# PIN2DMD.net
KiCad netlist of a schematic drawn in EAGLE
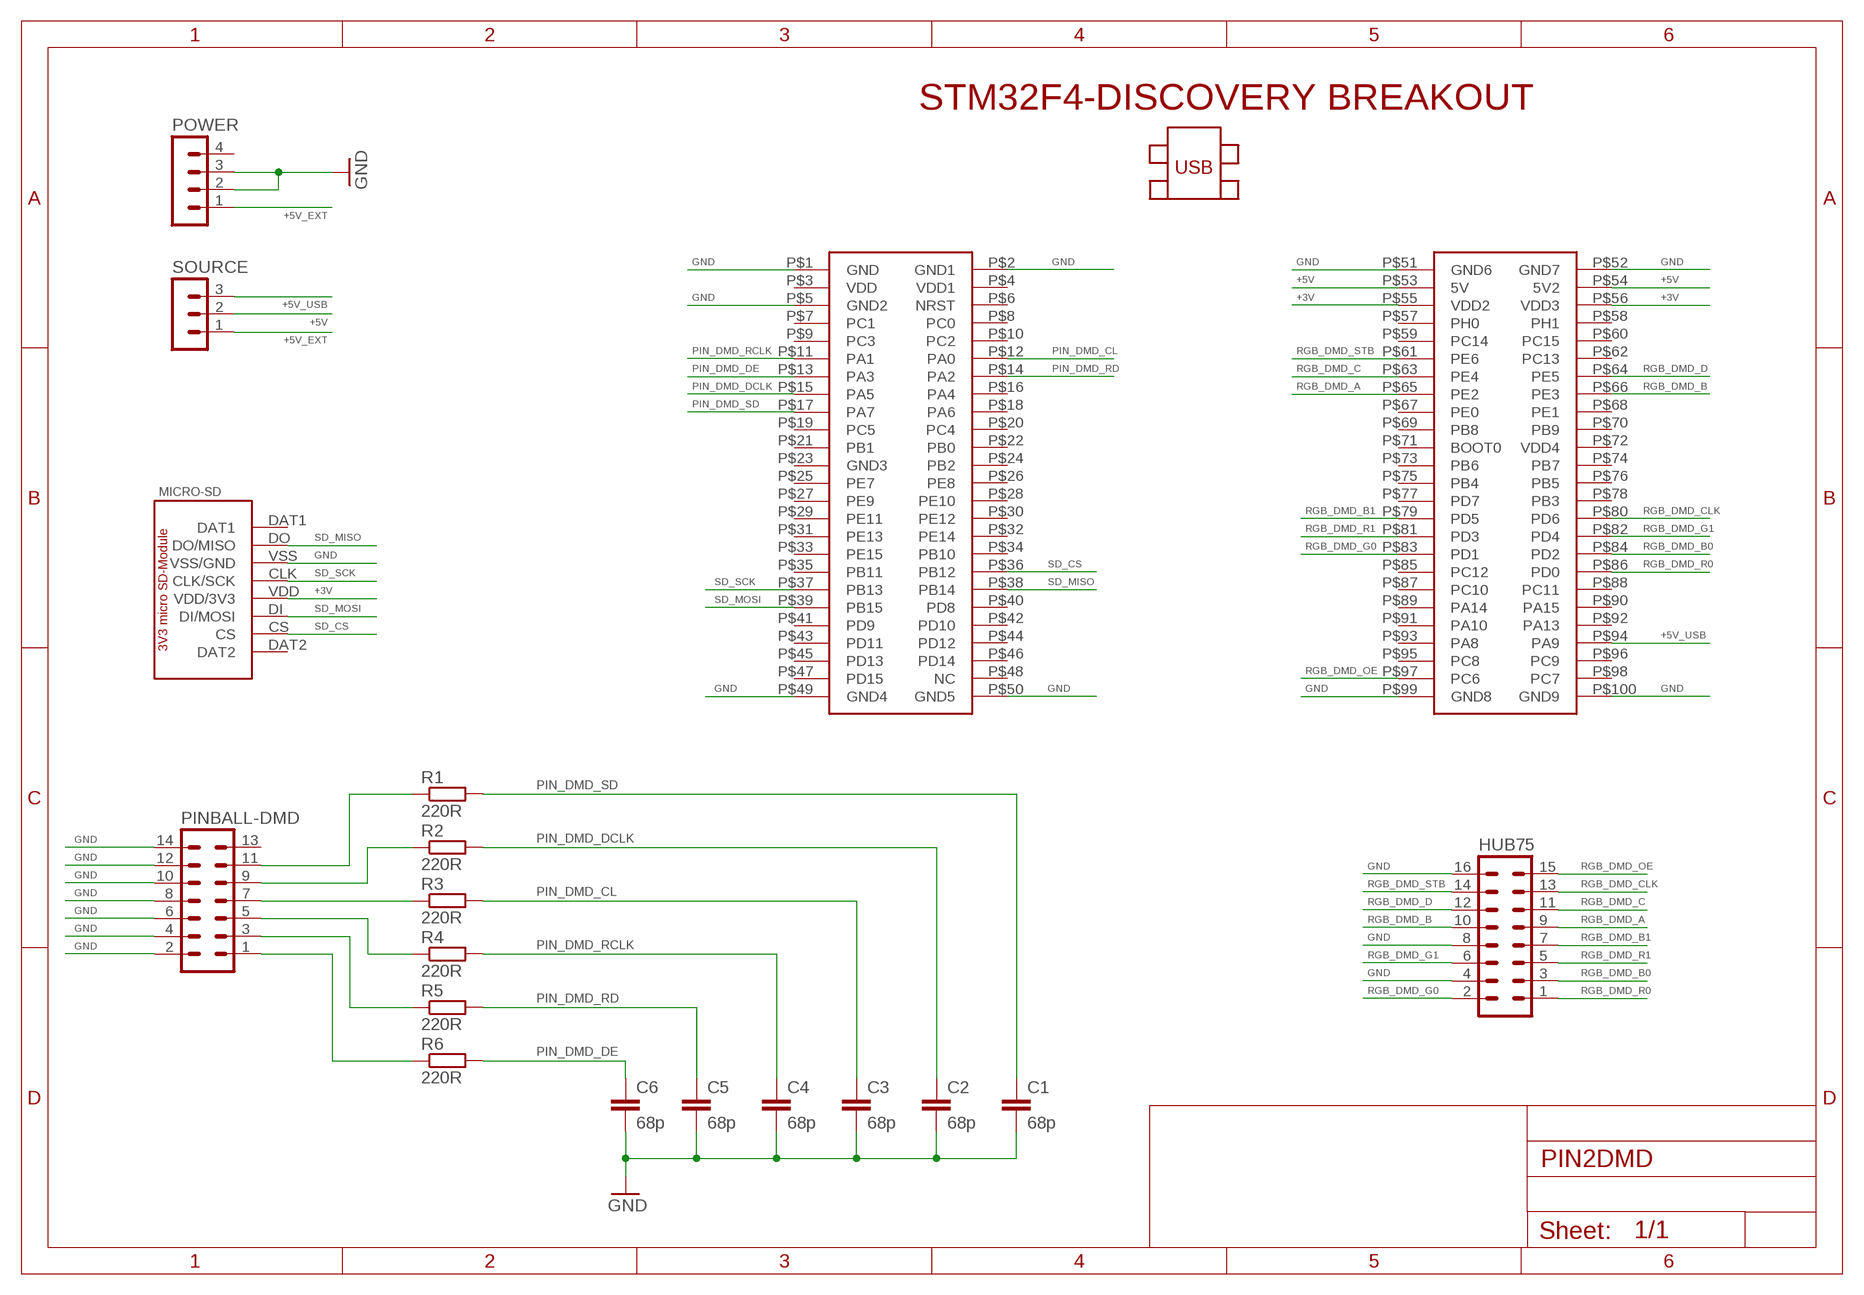
[diagram p0: schematic, sheet 1]

(export (version "E")
  (design (tool "Eeschema 10.0.6"))
  (components
    (comp (ref "C1")
      (value "68p")
      (footprint "eagle-import:C025-024X044")
      (libsource (lib "eagle-import") (part "C-EU025-024X044"))
    )
    (comp (ref "C2")
      (value "68p")
      (footprint "eagle-import:C025-024X044")
      (libsource (lib "eagle-import") (part "C-EU025-024X044"))
    )
    (comp (ref "C3")
      (value "68p")
      (footprint "eagle-import:C025-024X044")
      (libsource (lib "eagle-import") (part "C-EU025-024X044"))
    )
    (comp (ref "C4")
      (value "68p")
      (footprint "eagle-import:C025-024X044")
      (libsource (lib "eagle-import") (part "C-EU025-024X044"))
    )
    (comp (ref "C5")
      (value "68p")
      (footprint "eagle-import:C025-024X044")
      (libsource (lib "eagle-import") (part "C-EU025-024X044"))
    )
    (comp (ref "C6")
      (value "68p")
      (footprint "eagle-import:C025-024X044")
      (libsource (lib "eagle-import") (part "C-EU025-024X044"))
    )
    (comp (ref "HUB75")
      (value "MA08-2")
      (footprint "eagle-import:MA08-2")
      (libsource (lib "eagle-import") (part "MA08-2"))
    )
    (comp (ref "MICRO-SD")
      (value "SPI_SDCARD_3V3_MICRO")
      (footprint "eagle-import:SPI_SDCARD_3V3_MICRO")
      (libsource (lib "eagle-import") (part "SPI_SDCARD_3V3_MICRO"))
    )
    (comp (ref "PINBALL-DMD")
      (value "MA07-2")
      (footprint "eagle-import:MA07-2")
      (libsource (lib "eagle-import") (part "MA07-2"))
    )
    (comp (ref "POWER")
      (value "MA04-1")
      (footprint "eagle-import:MA04-1")
      (libsource (lib "eagle-import") (part "MA04-1"))
    )
    (comp (ref "R1")
      (value "220R")
      (footprint "eagle-import:0207_10")
      (libsource (lib "eagle-import") (part "R-EU_0207/10"))
    )
    (comp (ref "R2")
      (value "220R")
      (footprint "eagle-import:0207_10")
      (libsource (lib "eagle-import") (part "R-EU_0207/10"))
    )
    (comp (ref "R3")
      (value "220R")
      (footprint "eagle-import:0207_10")
      (libsource (lib "eagle-import") (part "R-EU_0207/10"))
    )
    (comp (ref "R4")
      (value "220R")
      (footprint "eagle-import:0207_10")
      (libsource (lib "eagle-import") (part "R-EU_0207/10"))
    )
    (comp (ref "R5")
      (value "220R")
      (footprint "eagle-import:0207_10")
      (libsource (lib "eagle-import") (part "R-EU_0207/10"))
    )
    (comp (ref "R6")
      (value "220R")
      (footprint "eagle-import:0207_10")
      (libsource (lib "eagle-import") (part "R-EU_0207/10"))
    )
    (comp (ref "SOURCE")
      (value "MA03-1")
      (footprint "eagle-import:MA03-1")
      (libsource (lib "eagle-import") (part "MA03-1"))
    )
    (comp (ref "U$1")
      (value "STM32F4-DISCOVERY")
      (footprint "eagle-import:STM32F4-DISCOVERY")
      (libsource (lib "eagle-import") (part "STM32F4-DISCOVERY"))
    )
  )
  (nets
    (net (code "1") (name "/+3V") (class "Default")
      (node (ref "MICRO-SD") (pin "VDD") (pinfunction "VDD/3V3_VDD") (pintype "input"))
      (node (ref "U$1") (pin "P$55") (pinfunction "VDD2_P$55") (pintype "bidirectional"))
      (node (ref "U$1") (pin "P$56") (pinfunction "VDD3_P$56") (pintype "bidirectional"))
    )
    (net (code "2") (name "/+5V") (class "Default")
      (node (ref "SOURCE") (pin "2") (pinfunction "2_2") (pintype "passive"))
      (node (ref "U$1") (pin "P$53") (pinfunction "5V_P$53") (pintype "bidirectional"))
      (node (ref "U$1") (pin "P$54") (pinfunction "5V2_P$54") (pintype "bidirectional"))
    )
    (net (code "3") (name "/+5V_EXT") (class "Default")
      (node (ref "POWER") (pin "1") (pinfunction "1_1") (pintype "passive"))
      (node (ref "SOURCE") (pin "1") (pinfunction "1_1") (pintype "passive"))
    )
    (net (code "4") (name "/+5V_USB") (class "Default")
      (node (ref "SOURCE") (pin "3") (pinfunction "3_3") (pintype "passive"))
      (node (ref "U$1") (pin "P$94") (pinfunction "PA9_P$94") (pintype "bidirectional"))
    )
    (net (code "5") (name "/PIN_DMD_CL") (class "Default")
      (node (ref "C3") (pin "1") (pinfunction "1_1") (pintype "passive"))
      (node (ref "R3") (pin "2") (pinfunction "2_2") (pintype "passive"))
      (node (ref "U$1") (pin "P$12") (pinfunction "PA0_P$12") (pintype "bidirectional"))
    )
    (net (code "6") (name "/PIN_DMD_DCLK") (class "Default")
      (node (ref "C2") (pin "1") (pinfunction "1_1") (pintype "passive"))
      (node (ref "R2") (pin "2") (pinfunction "2_2") (pintype "passive"))
      (node (ref "U$1") (pin "P$15") (pinfunction "PA5_P$15") (pintype "bidirectional"))
    )
    (net (code "7") (name "/PIN_DMD_DE") (class "Default")
      (node (ref "C6") (pin "1") (pinfunction "1_1") (pintype "passive"))
      (node (ref "R6") (pin "2") (pinfunction "2_2") (pintype "passive"))
      (node (ref "U$1") (pin "P$13") (pinfunction "PA3_P$13") (pintype "bidirectional"))
    )
    (net (code "8") (name "/PIN_DMD_RCLK") (class "Default")
      (node (ref "C4") (pin "1") (pinfunction "1_1") (pintype "passive"))
      (node (ref "R4") (pin "2") (pinfunction "2_2") (pintype "passive"))
      (node (ref "U$1") (pin "P$11") (pinfunction "PA1_P$11") (pintype "bidirectional"))
    )
    (net (code "9") (name "/PIN_DMD_RD") (class "Default")
      (node (ref "C5") (pin "1") (pinfunction "1_1") (pintype "passive"))
      (node (ref "R5") (pin "2") (pinfunction "2_2") (pintype "passive"))
      (node (ref "U$1") (pin "P$14") (pinfunction "PA2_P$14") (pintype "bidirectional"))
    )
    (net (code "10") (name "/PIN_DMD_SD") (class "Default")
      (node (ref "C1") (pin "1") (pinfunction "1_1") (pintype "passive"))
      (node (ref "R1") (pin "2") (pinfunction "2_2") (pintype "passive"))
      (node (ref "U$1") (pin "P$17") (pinfunction "PA7_P$17") (pintype "bidirectional"))
    )
    (net (code "11") (name "/RGB_DMD_A") (class "Default")
      (node (ref "HUB75") (pin "9") (pinfunction "9_9") (pintype "passive"))
      (node (ref "U$1") (pin "P$65") (pinfunction "PE2_P$65") (pintype "bidirectional"))
    )
    (net (code "12") (name "/RGB_DMD_B") (class "Default")
      (node (ref "HUB75") (pin "10") (pinfunction "10_10") (pintype "passive"))
      (node (ref "U$1") (pin "P$66") (pinfunction "PE3_P$66") (pintype "bidirectional"))
    )
    (net (code "13") (name "/RGB_DMD_B0") (class "Default")
      (node (ref "HUB75") (pin "3") (pinfunction "3_3") (pintype "passive"))
      (node (ref "U$1") (pin "P$84") (pinfunction "PD2_P$84") (pintype "bidirectional"))
    )
    (net (code "14") (name "/RGB_DMD_B1") (class "Default")
      (node (ref "HUB75") (pin "7") (pinfunction "7_7") (pintype "passive"))
      (node (ref "U$1") (pin "P$79") (pinfunction "PD5_P$79") (pintype "bidirectional"))
    )
    (net (code "15") (name "/RGB_DMD_C") (class "Default")
      (node (ref "HUB75") (pin "11") (pinfunction "11_11") (pintype "passive"))
      (node (ref "U$1") (pin "P$63") (pinfunction "PE4_P$63") (pintype "bidirectional"))
    )
    (net (code "16") (name "/RGB_DMD_CLK") (class "Default")
      (node (ref "HUB75") (pin "13") (pinfunction "13_13") (pintype "passive"))
      (node (ref "U$1") (pin "P$80") (pinfunction "PD6_P$80") (pintype "bidirectional"))
    )
    (net (code "17") (name "/RGB_DMD_D") (class "Default")
      (node (ref "HUB75") (pin "12") (pinfunction "12_12") (pintype "passive"))
      (node (ref "U$1") (pin "P$64") (pinfunction "PE5_P$64") (pintype "bidirectional"))
    )
    (net (code "18") (name "/RGB_DMD_G0") (class "Default")
      (node (ref "HUB75") (pin "2") (pinfunction "2_2") (pintype "passive"))
      (node (ref "U$1") (pin "P$83") (pinfunction "PD1_P$83") (pintype "bidirectional"))
    )
    (net (code "19") (name "/RGB_DMD_G1") (class "Default")
      (node (ref "HUB75") (pin "6") (pinfunction "6_6") (pintype "passive"))
      (node (ref "U$1") (pin "P$82") (pinfunction "PD4_P$82") (pintype "bidirectional"))
    )
    (net (code "20") (name "/RGB_DMD_OE") (class "Default")
      (node (ref "HUB75") (pin "15") (pinfunction "15_15") (pintype "passive"))
      (node (ref "U$1") (pin "P$97") (pinfunction "PC6_P$97") (pintype "bidirectional"))
    )
    (net (code "21") (name "/RGB_DMD_R0") (class "Default")
      (node (ref "HUB75") (pin "1") (pinfunction "1_1") (pintype "passive"))
      (node (ref "U$1") (pin "P$86") (pinfunction "PD0_P$86") (pintype "bidirectional"))
    )
    (net (code "22") (name "/RGB_DMD_R1") (class "Default")
      (node (ref "HUB75") (pin "5") (pinfunction "5_5") (pintype "passive"))
      (node (ref "U$1") (pin "P$81") (pinfunction "PD3_P$81") (pintype "bidirectional"))
    )
    (net (code "23") (name "/RGB_DMD_STB") (class "Default")
      (node (ref "HUB75") (pin "14") (pinfunction "14_14") (pintype "passive"))
      (node (ref "U$1") (pin "P$61") (pinfunction "PE6_P$61") (pintype "bidirectional"))
    )
    (net (code "24") (name "/SD_CS") (class "Default")
      (node (ref "MICRO-SD") (pin "CS") (pinfunction "CS_CS") (pintype "input"))
      (node (ref "U$1") (pin "P$36") (pinfunction "PB12_P$36") (pintype "bidirectional"))
    )
    (net (code "25") (name "/SD_MISO") (class "Default")
      (node (ref "MICRO-SD") (pin "DO") (pinfunction "DO/MISO_DO") (pintype "bidirectional"))
      (node (ref "U$1") (pin "P$38") (pinfunction "PB14_P$38") (pintype "bidirectional"))
    )
    (net (code "26") (name "/SD_MOSI") (class "Default")
      (node (ref "MICRO-SD") (pin "DI") (pinfunction "DI/MOSI_DI") (pintype "input"))
      (node (ref "U$1") (pin "P$39") (pinfunction "PB15_P$39") (pintype "bidirectional"))
    )
    (net (code "27") (name "/SD_SCK") (class "Default")
      (node (ref "MICRO-SD") (pin "CLK") (pinfunction "CLK/SCK_CLK") (pintype "input"))
      (node (ref "U$1") (pin "P$37") (pinfunction "PB13_P$37") (pintype "bidirectional"))
    )
    (net (code "28") (name "GND") (class "Default")
      (node (ref "C1") (pin "2") (pinfunction "2_2") (pintype "passive"))
      (node (ref "C2") (pin "2") (pinfunction "2_2") (pintype "passive"))
      (node (ref "C3") (pin "2") (pinfunction "2_2") (pintype "passive"))
      (node (ref "C4") (pin "2") (pinfunction "2_2") (pintype "passive"))
      (node (ref "C5") (pin "2") (pinfunction "2_2") (pintype "passive"))
      (node (ref "C6") (pin "2") (pinfunction "2_2") (pintype "passive"))
      (node (ref "HUB75") (pin "16") (pinfunction "16_16") (pintype "passive"))
      (node (ref "HUB75") (pin "4") (pinfunction "4_4") (pintype "passive"))
      (node (ref "HUB75") (pin "8") (pinfunction "8_8") (pintype "passive"))
      (node (ref "MICRO-SD") (pin "VSS") (pinfunction "VSS/GND_VSS") (pintype "input"))
      (node (ref "PINBALL-DMD") (pin "10") (pinfunction "10_10") (pintype "passive"))
      (node (ref "PINBALL-DMD") (pin "12") (pinfunction "12_12") (pintype "passive"))
      (node (ref "PINBALL-DMD") (pin "14") (pinfunction "14_14") (pintype "passive"))
      (node (ref "PINBALL-DMD") (pin "2") (pinfunction "2_2") (pintype "passive"))
      (node (ref "PINBALL-DMD") (pin "4") (pinfunction "4_4") (pintype "passive"))
      (node (ref "PINBALL-DMD") (pin "6") (pinfunction "6_6") (pintype "passive"))
      (node (ref "PINBALL-DMD") (pin "8") (pinfunction "8_8") (pintype "passive"))
      (node (ref "POWER") (pin "2") (pinfunction "2_2") (pintype "passive"))
      (node (ref "POWER") (pin "3") (pinfunction "3_3") (pintype "passive"))
      (node (ref "U$1") (pin "P$1") (pinfunction "GND_P$1") (pintype "bidirectional"))
      (node (ref "U$1") (pin "P$100") (pinfunction "GND9_P$100") (pintype "bidirectional"))
      (node (ref "U$1") (pin "P$2") (pinfunction "GND1_P$2") (pintype "bidirectional"))
      (node (ref "U$1") (pin "P$49") (pinfunction "GND4_P$49") (pintype "bidirectional"))
      (node (ref "U$1") (pin "P$5") (pinfunction "GND2_P$5") (pintype "bidirectional"))
      (node (ref "U$1") (pin "P$50") (pinfunction "GND5_P$50") (pintype "bidirectional"))
      (node (ref "U$1") (pin "P$51") (pinfunction "GND6_P$51") (pintype "bidirectional"))
      (node (ref "U$1") (pin "P$52") (pinfunction "GND7_P$52") (pintype "bidirectional"))
      (node (ref "U$1") (pin "P$99") (pinfunction "GND8_P$99") (pintype "bidirectional"))
    )
    (net (code "29") (name "Net-(PINBALL-DMD-Pad1)") (class "Default")
      (node (ref "PINBALL-DMD") (pin "1") (pinfunction "1_1") (pintype "passive"))
      (node (ref "R6") (pin "1") (pinfunction "1_1") (pintype "passive"))
    )
    (net (code "30") (name "Net-(PINBALL-DMD-Pad3)") (class "Default")
      (node (ref "PINBALL-DMD") (pin "3") (pinfunction "3_3") (pintype "passive"))
      (node (ref "R5") (pin "1") (pinfunction "1_1") (pintype "passive"))
    )
    (net (code "31") (name "Net-(PINBALL-DMD-Pad5)") (class "Default")
      (node (ref "PINBALL-DMD") (pin "5") (pinfunction "5_5") (pintype "passive"))
      (node (ref "R4") (pin "1") (pinfunction "1_1") (pintype "passive"))
    )
    (net (code "32") (name "Net-(PINBALL-DMD-Pad7)") (class "Default")
      (node (ref "PINBALL-DMD") (pin "7") (pinfunction "7_7") (pintype "passive"))
      (node (ref "R3") (pin "1") (pinfunction "1_1") (pintype "passive"))
    )
    (net (code "33") (name "Net-(PINBALL-DMD-Pad9)") (class "Default")
      (node (ref "PINBALL-DMD") (pin "9") (pinfunction "9_9") (pintype "passive"))
      (node (ref "R2") (pin "1") (pinfunction "1_1") (pintype "passive"))
    )
    (net (code "34") (name "Net-(PINBALL-DMD-Pad11)") (class "Default")
      (node (ref "PINBALL-DMD") (pin "11") (pinfunction "11_11") (pintype "passive"))
      (node (ref "R1") (pin "1") (pinfunction "1_1") (pintype "passive"))
    )
    (net (code "35") (name "unconnected-(MICRO-SD-PadDAT1)") (class "Default")
      (node (ref "MICRO-SD") (pin "DAT1") (pinfunction "DAT1_DAT1") (pintype "bidirectional"))
    )
    (net (code "36") (name "unconnected-(MICRO-SD-PadDAT2)") (class "Default")
      (node (ref "MICRO-SD") (pin "DAT2") (pinfunction "DAT2_DAT2") (pintype "input"))
    )
    (net (code "37") (name "unconnected-(PINBALL-DMD-Pad13)") (class "Default")
      (node (ref "PINBALL-DMD") (pin "13") (pinfunction "13_13") (pintype "passive"))
    )
    (net (code "38") (name "unconnected-(POWER-Pad4)") (class "Default")
      (node (ref "POWER") (pin "4") (pinfunction "4_4") (pintype "passive"))
    )
    (net (code "39") (name "unconnected-(U$1-BOOT0-PadP$71)") (class "Default")
      (node (ref "U$1") (pin "P$71") (pinfunction "BOOT0_P$71") (pintype "bidirectional"))
    )
    (net (code "40") (name "unconnected-(U$1-GND3-PadP$23)") (class "Default")
      (node (ref "U$1") (pin "P$23") (pinfunction "GND3_P$23") (pintype "bidirectional"))
    )
    (net (code "41") (name "unconnected-(U$1-NC-PadP$48)") (class "Default")
      (node (ref "U$1") (pin "P$48") (pinfunction "NC_P$48") (pintype "bidirectional"))
    )
    (net (code "42") (name "unconnected-(U$1-NRST-PadP$6)") (class "Default")
      (node (ref "U$1") (pin "P$6") (pinfunction "NRST_P$6") (pintype "bidirectional"))
    )
    (net (code "43") (name "unconnected-(U$1-PA4-PadP$16)") (class "Default")
      (node (ref "U$1") (pin "P$16") (pinfunction "PA4_P$16") (pintype "bidirectional"))
    )
    (net (code "44") (name "unconnected-(U$1-PA6-PadP$18)") (class "Default")
      (node (ref "U$1") (pin "P$18") (pinfunction "PA6_P$18") (pintype "bidirectional"))
    )
    (net (code "45") (name "unconnected-(U$1-PA8-PadP$93)") (class "Default")
      (node (ref "U$1") (pin "P$93") (pinfunction "PA8_P$93") (pintype "bidirectional"))
    )
    (net (code "46") (name "unconnected-(U$1-PA10-PadP$91)") (class "Default")
      (node (ref "U$1") (pin "P$91") (pinfunction "PA10_P$91") (pintype "bidirectional"))
    )
    (net (code "47") (name "unconnected-(U$1-PA13-PadP$92)") (class "Default")
      (node (ref "U$1") (pin "P$92") (pinfunction "PA13_P$92") (pintype "bidirectional"))
    )
    (net (code "48") (name "unconnected-(U$1-PA14-PadP$89)") (class "Default")
      (node (ref "U$1") (pin "P$89") (pinfunction "PA14_P$89") (pintype "bidirectional"))
    )
    (net (code "49") (name "unconnected-(U$1-PA15-PadP$90)") (class "Default")
      (node (ref "U$1") (pin "P$90") (pinfunction "PA15_P$90") (pintype "bidirectional"))
    )
    (net (code "50") (name "unconnected-(U$1-PB0-PadP$22)") (class "Default")
      (node (ref "U$1") (pin "P$22") (pinfunction "PB0_P$22") (pintype "bidirectional"))
    )
    (net (code "51") (name "unconnected-(U$1-PB1-PadP$21)") (class "Default")
      (node (ref "U$1") (pin "P$21") (pinfunction "PB1_P$21") (pintype "bidirectional"))
    )
    (net (code "52") (name "unconnected-(U$1-PB2-PadP$24)") (class "Default")
      (node (ref "U$1") (pin "P$24") (pinfunction "PB2_P$24") (pintype "bidirectional"))
    )
    (net (code "53") (name "unconnected-(U$1-PB3-PadP$78)") (class "Default")
      (node (ref "U$1") (pin "P$78") (pinfunction "PB3_P$78") (pintype "bidirectional"))
    )
    (net (code "54") (name "unconnected-(U$1-PB4-PadP$75)") (class "Default")
      (node (ref "U$1") (pin "P$75") (pinfunction "PB4_P$75") (pintype "bidirectional"))
    )
    (net (code "55") (name "unconnected-(U$1-PB5-PadP$76)") (class "Default")
      (node (ref "U$1") (pin "P$76") (pinfunction "PB5_P$76") (pintype "bidirectional"))
    )
    (net (code "56") (name "unconnected-(U$1-PB6-PadP$73)") (class "Default")
      (node (ref "U$1") (pin "P$73") (pinfunction "PB6_P$73") (pintype "bidirectional"))
    )
    (net (code "57") (name "unconnected-(U$1-PB7-PadP$74)") (class "Default")
      (node (ref "U$1") (pin "P$74") (pinfunction "PB7_P$74") (pintype "bidirectional"))
    )
    (net (code "58") (name "unconnected-(U$1-PB8-PadP$69)") (class "Default")
      (node (ref "U$1") (pin "P$69") (pinfunction "PB8_P$69") (pintype "bidirectional"))
    )
    (net (code "59") (name "unconnected-(U$1-PB9-PadP$70)") (class "Default")
      (node (ref "U$1") (pin "P$70") (pinfunction "PB9_P$70") (pintype "bidirectional"))
    )
    (net (code "60") (name "unconnected-(U$1-PB10-PadP$34)") (class "Default")
      (node (ref "U$1") (pin "P$34") (pinfunction "PB10_P$34") (pintype "bidirectional"))
    )
    (net (code "61") (name "unconnected-(U$1-PB11-PadP$35)") (class "Default")
      (node (ref "U$1") (pin "P$35") (pinfunction "PB11_P$35") (pintype "bidirectional"))
    )
    (net (code "62") (name "unconnected-(U$1-PC0-PadP$8)") (class "Default")
      (node (ref "U$1") (pin "P$8") (pinfunction "PC0_P$8") (pintype "bidirectional"))
    )
    (net (code "63") (name "unconnected-(U$1-PC1-PadP$7)") (class "Default")
      (node (ref "U$1") (pin "P$7") (pinfunction "PC1_P$7") (pintype "bidirectional"))
    )
    (net (code "64") (name "unconnected-(U$1-PC2-PadP$10)") (class "Default")
      (node (ref "U$1") (pin "P$10") (pinfunction "PC2_P$10") (pintype "bidirectional"))
    )
    (net (code "65") (name "unconnected-(U$1-PC3-PadP$9)") (class "Default")
      (node (ref "U$1") (pin "P$9") (pinfunction "PC3_P$9") (pintype "bidirectional"))
    )
    (net (code "66") (name "unconnected-(U$1-PC4-PadP$20)") (class "Default")
      (node (ref "U$1") (pin "P$20") (pinfunction "PC4_P$20") (pintype "bidirectional"))
    )
    (net (code "67") (name "unconnected-(U$1-PC5-PadP$19)") (class "Default")
      (node (ref "U$1") (pin "P$19") (pinfunction "PC5_P$19") (pintype "bidirectional"))
    )
    (net (code "68") (name "unconnected-(U$1-PC7-PadP$98)") (class "Default")
      (node (ref "U$1") (pin "P$98") (pinfunction "PC7_P$98") (pintype "bidirectional"))
    )
    (net (code "69") (name "unconnected-(U$1-PC8-PadP$95)") (class "Default")
      (node (ref "U$1") (pin "P$95") (pinfunction "PC8_P$95") (pintype "bidirectional"))
    )
    (net (code "70") (name "unconnected-(U$1-PC9-PadP$96)") (class "Default")
      (node (ref "U$1") (pin "P$96") (pinfunction "PC9_P$96") (pintype "bidirectional"))
    )
    (net (code "71") (name "unconnected-(U$1-PC10-PadP$87)") (class "Default")
      (node (ref "U$1") (pin "P$87") (pinfunction "PC10_P$87") (pintype "bidirectional"))
    )
    (net (code "72") (name "unconnected-(U$1-PC11-PadP$88)") (class "Default")
      (node (ref "U$1") (pin "P$88") (pinfunction "PC11_P$88") (pintype "bidirectional"))
    )
    (net (code "73") (name "unconnected-(U$1-PC12-PadP$85)") (class "Default")
      (node (ref "U$1") (pin "P$85") (pinfunction "PC12_P$85") (pintype "bidirectional"))
    )
    (net (code "74") (name "unconnected-(U$1-PC13-PadP$62)") (class "Default")
      (node (ref "U$1") (pin "P$62") (pinfunction "PC13_P$62") (pintype "bidirectional"))
    )
    (net (code "75") (name "unconnected-(U$1-PC14-PadP$59)") (class "Default")
      (node (ref "U$1") (pin "P$59") (pinfunction "PC14_P$59") (pintype "bidirectional"))
    )
    (net (code "76") (name "unconnected-(U$1-PC15-PadP$60)") (class "Default")
      (node (ref "U$1") (pin "P$60") (pinfunction "PC15_P$60") (pintype "bidirectional"))
    )
    (net (code "77") (name "unconnected-(U$1-PD7-PadP$77)") (class "Default")
      (node (ref "U$1") (pin "P$77") (pinfunction "PD7_P$77") (pintype "bidirectional"))
    )
    (net (code "78") (name "unconnected-(U$1-PD8-PadP$40)") (class "Default")
      (node (ref "U$1") (pin "P$40") (pinfunction "PD8_P$40") (pintype "bidirectional"))
    )
    (net (code "79") (name "unconnected-(U$1-PD9-PadP$41)") (class "Default")
      (node (ref "U$1") (pin "P$41") (pinfunction "PD9_P$41") (pintype "bidirectional"))
    )
    (net (code "80") (name "unconnected-(U$1-PD10-PadP$42)") (class "Default")
      (node (ref "U$1") (pin "P$42") (pinfunction "PD10_P$42") (pintype "bidirectional"))
    )
    (net (code "81") (name "unconnected-(U$1-PD11-PadP$43)") (class "Default")
      (node (ref "U$1") (pin "P$43") (pinfunction "PD11_P$43") (pintype "bidirectional"))
    )
    (net (code "82") (name "unconnected-(U$1-PD12-PadP$44)") (class "Default")
      (node (ref "U$1") (pin "P$44") (pinfunction "PD12_P$44") (pintype "bidirectional"))
    )
    (net (code "83") (name "unconnected-(U$1-PD13-PadP$45)") (class "Default")
      (node (ref "U$1") (pin "P$45") (pinfunction "PD13_P$45") (pintype "bidirectional"))
    )
    (net (code "84") (name "unconnected-(U$1-PD14-PadP$46)") (class "Default")
      (node (ref "U$1") (pin "P$46") (pinfunction "PD14_P$46") (pintype "bidirectional"))
    )
    (net (code "85") (name "unconnected-(U$1-PD15-PadP$47)") (class "Default")
      (node (ref "U$1") (pin "P$47") (pinfunction "PD15_P$47") (pintype "bidirectional"))
    )
    (net (code "86") (name "unconnected-(U$1-PE0-PadP$67)") (class "Default")
      (node (ref "U$1") (pin "P$67") (pinfunction "PE0_P$67") (pintype "bidirectional"))
    )
    (net (code "87") (name "unconnected-(U$1-PE1-PadP$68)") (class "Default")
      (node (ref "U$1") (pin "P$68") (pinfunction "PE1_P$68") (pintype "bidirectional"))
    )
    (net (code "88") (name "unconnected-(U$1-PE7-PadP$25)") (class "Default")
      (node (ref "U$1") (pin "P$25") (pinfunction "PE7_P$25") (pintype "bidirectional"))
    )
    (net (code "89") (name "unconnected-(U$1-PE8-PadP$26)") (class "Default")
      (node (ref "U$1") (pin "P$26") (pinfunction "PE8_P$26") (pintype "bidirectional"))
    )
    (net (code "90") (name "unconnected-(U$1-PE9-PadP$27)") (class "Default")
      (node (ref "U$1") (pin "P$27") (pinfunction "PE9_P$27") (pintype "bidirectional"))
    )
    (net (code "91") (name "unconnected-(U$1-PE10-PadP$28)") (class "Default")
      (node (ref "U$1") (pin "P$28") (pinfunction "PE10_P$28") (pintype "bidirectional"))
    )
    (net (code "92") (name "unconnected-(U$1-PE11-PadP$29)") (class "Default")
      (node (ref "U$1") (pin "P$29") (pinfunction "PE11_P$29") (pintype "bidirectional"))
    )
    (net (code "93") (name "unconnected-(U$1-PE12-PadP$30)") (class "Default")
      (node (ref "U$1") (pin "P$30") (pinfunction "PE12_P$30") (pintype "bidirectional"))
    )
    (net (code "94") (name "unconnected-(U$1-PE13-PadP$31)") (class "Default")
      (node (ref "U$1") (pin "P$31") (pinfunction "PE13_P$31") (pintype "bidirectional"))
    )
    (net (code "95") (name "unconnected-(U$1-PE14-PadP$32)") (class "Default")
      (node (ref "U$1") (pin "P$32") (pinfunction "PE14_P$32") (pintype "bidirectional"))
    )
    (net (code "96") (name "unconnected-(U$1-PE15-PadP$33)") (class "Default")
      (node (ref "U$1") (pin "P$33") (pinfunction "PE15_P$33") (pintype "bidirectional"))
    )
    (net (code "97") (name "unconnected-(U$1-PH0-PadP$57)") (class "Default")
      (node (ref "U$1") (pin "P$57") (pinfunction "PH0_P$57") (pintype "bidirectional"))
    )
    (net (code "98") (name "unconnected-(U$1-PH1-PadP$58)") (class "Default")
      (node (ref "U$1") (pin "P$58") (pinfunction "PH1_P$58") (pintype "bidirectional"))
    )
    (net (code "99") (name "unconnected-(U$1-VDD-PadP$3)") (class "Default")
      (node (ref "U$1") (pin "P$3") (pinfunction "VDD_P$3") (pintype "bidirectional"))
    )
    (net (code "100") (name "unconnected-(U$1-VDD1-PadP$4)") (class "Default")
      (node (ref "U$1") (pin "P$4") (pinfunction "VDD1_P$4") (pintype "bidirectional"))
    )
    (net (code "101") (name "unconnected-(U$1-VDD4-PadP$72)") (class "Default")
      (node (ref "U$1") (pin "P$72") (pinfunction "VDD4_P$72") (pintype "bidirectional"))
    )
  )
)
